# openSX70_LENS_BELLOWS_V5_1-SEEED_2018022.net
KiCad netlist of a schematic drawn in EAGLE
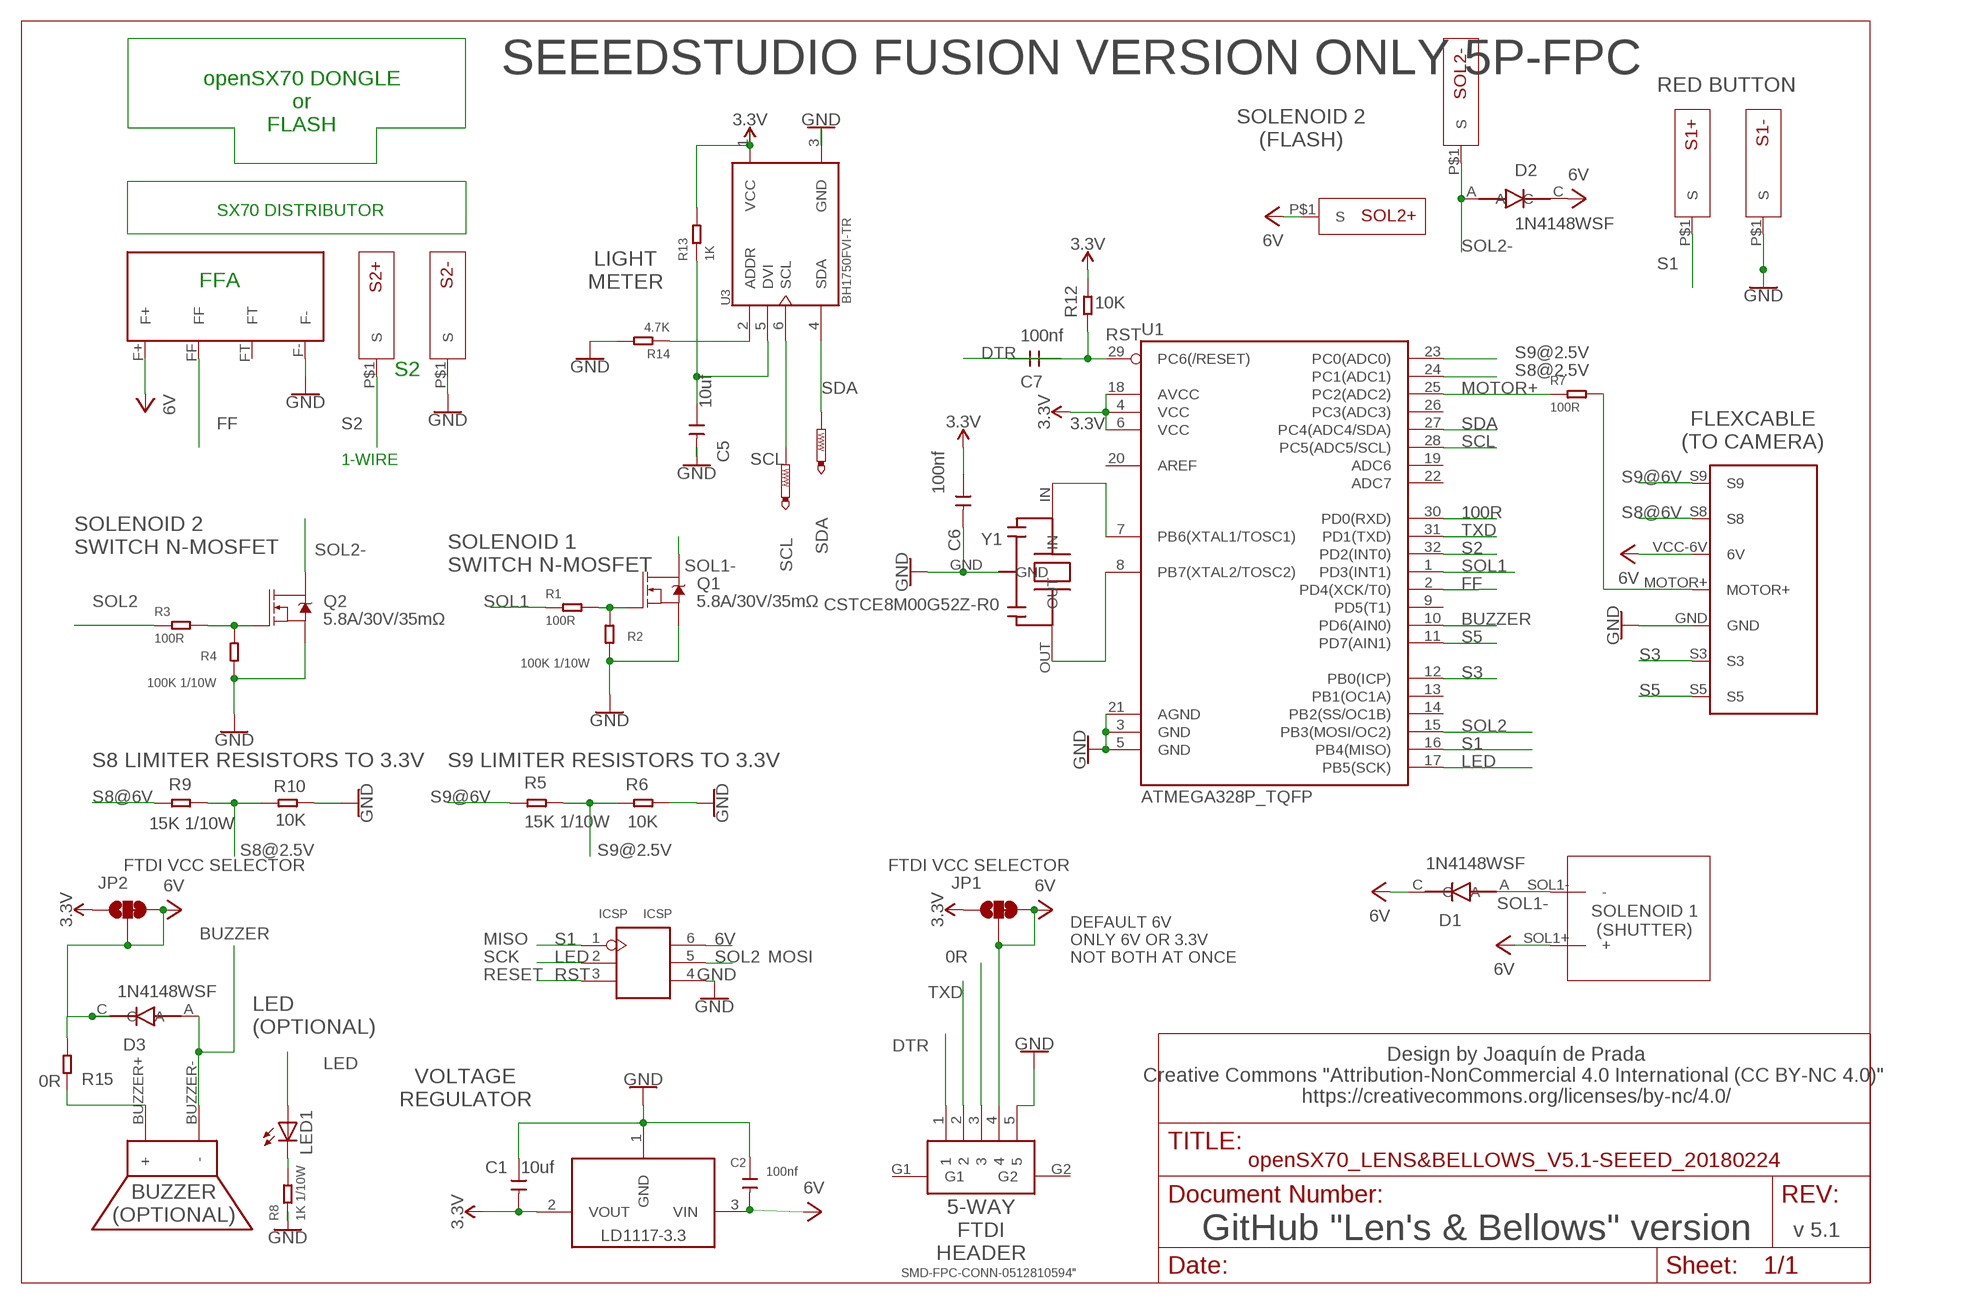
[diagram p0: schematic, sheet 1]

(export (version "E")
  (design (tool "Eeschema 10.0.6"))
  (components
    (comp (ref "C1")
      (value "10uf")
      (footprint "eagle-import:C0603")
      (fields (field (name "MPN") "CC0603KRX5R6BB106"))
      (libsource (lib "eagle-import") (part "CERAMIC-10UF-10V-10%-X5R(0603)"))
    )
    (comp (ref "C2")
      (value "100nf")
      (footprint "eagle-import:C0603")
      (fields (field (name "MPN") "CC0603KRX7R9BB104"))
      (libsource (lib "eagle-import") (part "CERAMIC-100NF-50V-10%-X7R(0603)"))
    )
    (comp (ref "C5")
      (value "10uf")
      (footprint "eagle-import:C0603")
      (fields (field (name "MPN") "CC0603KRX5R6BB106"))
      (libsource (lib "eagle-import") (part "CERAMIC-10UF-10V-10%-X5R(0603)"))
    )
    (comp (ref "C6")
      (value "100nf")
      (footprint "eagle-import:C0603")
      (fields (field (name "MPN") "CC0603KRX7R9BB104"))
      (libsource (lib "eagle-import") (part "CERAMIC-100NF-50V-10%-X7R(0603)"))
    )
    (comp (ref "C7")
      (value "100nf")
      (footprint "eagle-import:C0603")
      (fields (field (name "MPN") "CC0603KRX7R9BB104"))
      (libsource (lib "eagle-import") (part "CERAMIC-100NF-50V-10%-X7R(0603)"))
    )
    (comp (ref "D1")
      (value "1N4148WSF")
      (footprint "eagle-import:SODFL2512X100N")
      (fields (field (name "MANUFACTURER") "Fairchild Semiconductor"))
      (libsource (lib "eagle-import") (part "1N4148WS"))
    )
    (comp (ref "D2")
      (value "1N4148WSF")
      (footprint "eagle-import:SODFL2512X100N")
      (fields (field (name "MANUFACTURER") "Fairchild Semiconductor"))
      (libsource (lib "eagle-import") (part "1N4148WS"))
    )
    (comp (ref "D3")
      (value "1N4148WSF")
      (footprint "eagle-import:SODFL2512X100N")
      (fields (field (name "MANUFACTURER") "Fairchild Semiconductor"))
      (libsource (lib "eagle-import") (part "1N4148WS"))
    )
    (comp (ref "ICSP")
      (value "ICSP")
      (footprint "eagle-import:H2X3-2.54")
      (libsource (lib "eagle-import") (part "ICSP"))
    )
    (comp (ref "JP1")
      (value "FTDI VCC SELECTOR")
      (footprint "eagle-import:SMT-JUMPER_3_1-NC_TRACE_SILK")
      (libsource (lib "eagle-import") (part "JUMPER-SMT_3_1-NC_TRACE_SILK"))
    )
    (comp (ref "JP2")
      (value "FTDI VCC SELECTOR")
      (footprint "eagle-import:SMT-JUMPER_3_1-NC_TRACE_SILK")
      (libsource (lib "eagle-import") (part "JUMPER-SMT_3_1-NC_TRACE_SILK"))
    )
    (comp (ref "LD11172.5V")
      (value "LD1117 2.5V")
      (footprint "eagle-import:SOT223")
      (fields (field (name "MF") "Advanced Monolithic Systems") (field (name "MP") "AMS1117-5.0"))
      (libsource (lib "eagle-import") (part "LD1117-3.3"))
    )
    (comp (ref "LED1")
      (value "LEDCHIPLED_0805")
      (footprint "eagle-import:CHIPLED_0805")
      (libsource (lib "eagle-import") (part "LEDCHIPLED_0805"))
    )
    (comp (ref "Q1")
      (value "5.8A/30V/35mΩ")
      (footprint "eagle-import:SOT23-3")
      (libsource (lib "eagle-import") (part "MOSFET-NCH-AO3404A"))
    )
    (comp (ref "Q2")
      (value "5.8A/30V/35mΩ")
      (footprint "eagle-import:SOT23-3")
      (libsource (lib "eagle-import") (part "MOSFET-NCH-AO3404A"))
    )
    (comp (ref "R1")
      (value "100R")
      (footprint "eagle-import:R0603")
      (fields (field (name "MPN") "RC0603JR-07100RL"))
      (libsource (lib "eagle-import") (part "SMD-RES-100R-5%-1/10W(0603)"))
    )
    (comp (ref "R2")
      (value "100K 1/10W")
      (footprint "eagle-import:R0603")
      (fields (field (name "MPN") "RC0603JR-07100KL"))
      (libsource (lib "eagle-import") (part "SMD-RES-100K-5%-1/10W(0603)"))
    )
    (comp (ref "R3")
      (value "100R")
      (footprint "eagle-import:R0603")
      (fields (field (name "MPN") "RC0603JR-07100RL"))
      (libsource (lib "eagle-import") (part "SMD-RES-100R-5%-1/10W(0603)"))
    )
    (comp (ref "R4")
      (value "100K 1/10W")
      (footprint "eagle-import:R0603")
      (fields (field (name "MPN") "RC0603JR-07100KL"))
      (libsource (lib "eagle-import") (part "SMD-RES-100K-5%-1/10W(0603)"))
    )
    (comp (ref "R5")
      (value "15K 1/10W")
      (footprint "eagle-import:R0603")
      (fields (field (name "MPN") "RC0603FR-0715KL"))
      (libsource (lib "eagle-import") (part "SMD-RES-15K-1%-1/10W(0603)"))
    )
    (comp (ref "R6")
      (value "10K")
      (footprint "eagle-import:R0603")
      (fields (field (name "MPN") "RC0603FR-0710KL"))
      (libsource (lib "eagle-import") (part "SMD-RES-10K-1%-1/10W(0603)"))
    )
    (comp (ref "R7")
      (value "100R")
      (footprint "eagle-import:R0603")
      (fields (field (name "MPN") "RC0603JR-07100RL"))
      (libsource (lib "eagle-import") (part "SMD-RES-100R-5%-1/10W(0603)"))
    )
    (comp (ref "R8")
      (value "1K 1/10W")
      (footprint "eagle-import:R0603")
      (fields (field (name "MPN") "RC0603JR-071KL"))
      (libsource (lib "eagle-import") (part "SMD-RES-1K-5%-1/10W(0603)"))
    )
    (comp (ref "R9")
      (value "15K 1/10W")
      (footprint "eagle-import:R0603")
      (fields (field (name "MPN") "RC0603FR-0715KL"))
      (libsource (lib "eagle-import") (part "SMD-RES-15K-1%-1/10W(0603)"))
    )
    (comp (ref "R10")
      (value "10K")
      (footprint "eagle-import:R0603")
      (fields (field (name "MPN") "RC0603FR-0710KL"))
      (libsource (lib "eagle-import") (part "SMD-RES-10K-1%-1/10W(0603)"))
    )
    (comp (ref "R12")
      (value "10K")
      (footprint "eagle-import:R0603")
      (fields (field (name "MPN") "RC0603FR-0710KL"))
      (libsource (lib "eagle-import") (part "SMD-RES-10K-1%-1/10W(0603)"))
    )
    (comp (ref "R13")
      (value "1K")
      (footprint "eagle-import:R0603")
      (fields (field (name "MPN") "RC0603FR-071KL"))
      (libsource (lib "eagle-import") (part "SMD-RES-1K-1%-1/10W(0603)"))
    )
    (comp (ref "R14")
      (value "4.7K")
      (footprint "eagle-import:R0603")
      (fields (field (name "MPN") "RC0603JR-074K7L"))
      (libsource (lib "eagle-import") (part "SMD-RES-4.7K-5%-1/10W(0603)"))
    )
    (comp (ref "R15")
      (value "0R")
      (footprint "eagle-import:R0603")
      (fields (field (name "MPN") "RC0603JR-07100RL"))
      (libsource (lib "eagle-import") (part "SMD-RES-100R-5%-1/10W(0603)"))
    )
    (comp (ref "S1+")
      (value "SX70-S-PAD-NEW")
      (footprint "eagle-import:SX70-S-PAD2")
      (libsource (lib "eagle-import") (part "SX70-S-PAD-NEW"))
    )
    (comp (ref "S1-")
      (value "SX70-S-PAD-NEW")
      (footprint "eagle-import:SX70-S-PAD2")
      (libsource (lib "eagle-import") (part "SX70-S-PAD-NEW"))
    )
    (comp (ref "S2+")
      (value "SX70-S-PAD-NEW")
      (footprint "eagle-import:SX70-S-PAD2")
      (libsource (lib "eagle-import") (part "SX70-S-PAD-NEW"))
    )
    (comp (ref "S2-")
      (value "SX70-S-PAD-NEW")
      (footprint "eagle-import:SX70-S-PAD2")
      (libsource (lib "eagle-import") (part "SX70-S-PAD-NEW"))
    )
    (comp (ref "SCL")
      (value "PTR1TP08R")
      (footprint "eagle-import:TP08R")
      (libsource (lib "eagle-import") (part "PTR1TP08R"))
    )
    (comp (ref "SDA")
      (value "PTR1TP08R")
      (footprint "eagle-import:TP08R")
      (libsource (lib "eagle-import") (part "PTR1TP08R"))
    )
    (comp (ref "SOL1")
      (value "SX70-SOLENOID1-2PADS")
      (footprint "eagle-import:SX70-SOLENOID1-2")
      (libsource (lib "eagle-import") (part "SX70-SOLENOID1-2PADS"))
    )
    (comp (ref "SOL2+")
      (value "SX70-S-PAD-NEW")
      (footprint "eagle-import:SX70-S-PAD2")
      (libsource (lib "eagle-import") (part "SX70-S-PAD-NEW"))
    )
    (comp (ref "SOL2-")
      (value "SX70-S-PAD-NEW")
      (footprint "eagle-import:SX70-S-PAD2")
      (libsource (lib "eagle-import") (part "SX70-S-PAD-NEW"))
    )
    (comp (ref "U$1")
      (value "SX70-7-PAD")
      (footprint "eagle-import:SX70-7-PAD")
      (libsource (lib "eagle-import") (part "SX70-7-PAD"))
    )
    (comp (ref "U$2")
      (value "FFA")
      (footprint "eagle-import:FFA-PAD-PACKAGE")
      (libsource (lib "eagle-import") (part "SX70-FFA-PAD"))
    )
    (comp (ref "U$3")
      (value "CSET8-5G_V2")
      (footprint "eagle-import:CSET8-5G_PACKAGE")
      (libsource (lib "eagle-import") (part "CSET8-5G_V2"))
    )
    (comp (ref "U$4")
      (value "SMD-FPC-CONN-0512810594\"")
      (footprint "eagle-import:51281-0594")
      (libsource (lib "eagle-import") (part "SMD-FPC-CONN-0512810594{dblquote}"))
    )
    (comp (ref "U1")
      (value "ATMEGA328P_TQFP")
      (footprint "eagle-import:TQFP32-08")
      (libsource (lib "eagle-import") (part "ATMEGA328P_TQFP"))
    )
    (comp (ref "U3")
      (value "BH1750FVI-TR")
      (footprint "eagle-import:SOTFL50P300X75-6N")
      (fields (field (name "MF") "Rohm"))
      (libsource (lib "eagle-import") (part "BH1750FVI-TR"))
    )
    (comp (ref "Y1")
      (value "CSTCE8M00G52Z-R0")
      (footprint "eagle-import:CFP95P160X100-3N")
      (fields (field (name "MF") "Murata") (field (name "MP") "CSTCE16M0V53-R0"))
      (libsource (lib "eagle-import") (part "CSTCE16M0V53-R0"))
    )
  )
  (nets
    (net (code "1") (name "/0R") (class "Default")
      (node (ref "U$4") (pin "3") (pinfunction "3_3") (pintype "bidirectional"))
    )
    (net (code "2") (name "/100R") (class "Default")
      (node (ref "U1") (pin "30") (pinfunction "PD0(RXD)_30") (pintype "bidirectional"))
    )
    (net (code "3") (name "/BUZZER") (class "Default")
      (node (ref "D3") (pin "A") (pinfunction "A_A") (pintype "passive"))
      (node (ref "U$3") (pin "BUZZER-") (pinfunction "-_BUZZER-") (pintype "bidirectional"))
      (node (ref "U1") (pin "10") (pinfunction "PD6(AIN0)_10") (pintype "bidirectional"))
    )
    (net (code "4") (name "/DTR") (class "Default")
      (node (ref "C7") (pin "1") (pinfunction "1_1") (pintype "passive"))
      (node (ref "U$4") (pin "1") (pinfunction "1_1") (pintype "bidirectional"))
    )
    (net (code "5") (name "/FF") (class "Default")
      (node (ref "U$2") (pin "FF") (pinfunction "FF_FF") (pintype "bidirectional"))
      (node (ref "U1") (pin "2") (pinfunction "PD4(XCK/T0)_2") (pintype "bidirectional"))
    )
    (net (code "6") (name "/LED") (class "Default")
      (node (ref "ICSP") (pin "2") (pinfunction "SCK_2") (pintype "bidirectional"))
      (node (ref "LED1") (pin "A") (pinfunction "A_A") (pintype "passive"))
      (node (ref "U1") (pin "17") (pinfunction "PB5(SCK)_17") (pintype "bidirectional"))
    )
    (net (code "7") (name "/MOTOR+") (class "Default")
      (node (ref "R7") (pin "1") (pinfunction "1_1") (pintype "passive"))
      (node (ref "U1") (pin "25") (pinfunction "PC2(ADC2)_25") (pintype "bidirectional"))
    )
    (net (code "8") (name "/RST") (class "Default")
      (node (ref "C7") (pin "2") (pinfunction "2_2") (pintype "passive"))
      (node (ref "ICSP") (pin "3") (pinfunction "RST_3") (pintype "bidirectional"))
      (node (ref "R12") (pin "1") (pinfunction "1_1") (pintype "passive"))
      (node (ref "U1") (pin "29") (pinfunction "PC6(/RESET)_29") (pintype "bidirectional"))
    )
    (net (code "9") (name "/S1") (class "Default")
      (node (ref "ICSP") (pin "1") (pinfunction "MISO_1") (pintype "bidirectional"))
      (node (ref "S1+") (pin "P$1") (pinfunction "S_P$1") (pintype "bidirectional"))
      (node (ref "U1") (pin "16") (pinfunction "PB4(MISO)_16") (pintype "bidirectional"))
    )
    (net (code "10") (name "/S2") (class "Default")
      (node (ref "S2+") (pin "P$1") (pinfunction "S_P$1") (pintype "bidirectional"))
      (node (ref "U1") (pin "32") (pinfunction "PD2(INT0)_32") (pintype "bidirectional"))
    )
    (net (code "11") (name "/S3") (class "Default")
      (node (ref "U$1") (pin "S3") (pinfunction "S3_S3") (pintype "bidirectional"))
      (node (ref "U1") (pin "12") (pinfunction "PB0(ICP)_12") (pintype "bidirectional"))
    )
    (net (code "12") (name "/S5") (class "Default")
      (node (ref "U$1") (pin "S5") (pinfunction "S5_S5") (pintype "bidirectional"))
      (node (ref "U1") (pin "11") (pinfunction "PD7(AIN1)_11") (pintype "bidirectional"))
    )
    (net (code "13") (name "/S8@2.5V") (class "Default")
      (node (ref "R10") (pin "1") (pinfunction "1_1") (pintype "passive"))
      (node (ref "R9") (pin "2") (pinfunction "2_2") (pintype "passive"))
      (node (ref "U1") (pin "24") (pinfunction "PC1(ADC1)_24") (pintype "bidirectional"))
    )
    (net (code "14") (name "/S8@6V") (class "Default")
      (node (ref "R9") (pin "1") (pinfunction "1_1") (pintype "passive"))
      (node (ref "U$1") (pin "S8") (pinfunction "S8_S8") (pintype "bidirectional"))
    )
    (net (code "15") (name "/S9@2.5V") (class "Default")
      (node (ref "R5") (pin "2") (pinfunction "2_2") (pintype "passive"))
      (node (ref "R6") (pin "1") (pinfunction "1_1") (pintype "passive"))
      (node (ref "U1") (pin "23") (pinfunction "PC0(ADC0)_23") (pintype "bidirectional"))
    )
    (net (code "16") (name "/S9@6V") (class "Default")
      (node (ref "R5") (pin "1") (pinfunction "1_1") (pintype "passive"))
      (node (ref "U$1") (pin "S9") (pinfunction "S9_S9") (pintype "bidirectional"))
    )
    (net (code "17") (name "/SCL") (class "Default")
      (node (ref "SCL") (pin "TP") (pinfunction "TP_TP") (pintype "input"))
      (node (ref "U1") (pin "28") (pinfunction "PC5(ADC5/SCL)_28") (pintype "bidirectional"))
      (node (ref "U3") (pin "6") (pinfunction "SCL_6") (pintype "input"))
    )
    (net (code "18") (name "/SDA") (class "Default")
      (node (ref "SDA") (pin "TP") (pinfunction "TP_TP") (pintype "input"))
      (node (ref "U1") (pin "27") (pinfunction "PC4(ADC4/SDA)_27") (pintype "bidirectional"))
      (node (ref "U3") (pin "4") (pinfunction "SDA_4") (pintype "bidirectional"))
    )
    (net (code "19") (name "/SOL1") (class "Default")
      (node (ref "R1") (pin "1") (pinfunction "1_1") (pintype "passive"))
      (node (ref "U1") (pin "1") (pinfunction "PD3(INT1)_1") (pintype "bidirectional"))
    )
    (net (code "20") (name "/SOL1-") (class "Default")
      (node (ref "D1") (pin "A") (pinfunction "A_A") (pintype "passive"))
      (node (ref "Q1") (pin "3") (pinfunction "D_3") (pintype "bidirectional"))
      (node (ref "SOL1") (pin "SOL1-") (pinfunction "-_SOL1-") (pintype "bidirectional"))
    )
    (net (code "21") (name "/SOL2") (class "Default")
      (node (ref "ICSP") (pin "5") (pinfunction "MOSI_5") (pintype "bidirectional"))
      (node (ref "R3") (pin "1") (pinfunction "1_1") (pintype "passive"))
      (node (ref "U1") (pin "15") (pinfunction "PB3(MOSI/OC2)_15") (pintype "bidirectional"))
    )
    (net (code "22") (name "/SOL2-") (class "Default")
      (node (ref "D2") (pin "A") (pinfunction "A_A") (pintype "passive"))
      (node (ref "Q2") (pin "3") (pinfunction "D_3") (pintype "bidirectional"))
      (node (ref "SOL2-") (pin "P$1") (pinfunction "S_P$1") (pintype "bidirectional"))
    )
    (net (code "23") (name "/TXD") (class "Default")
      (node (ref "U$4") (pin "2") (pinfunction "2_2") (pintype "bidirectional"))
      (node (ref "U1") (pin "31") (pinfunction "PD1(TXD)_31") (pintype "bidirectional"))
    )
    (net (code "24") (name "3.3V") (class "Default")
      (node (ref "C1") (pin "2") (pinfunction "2_2") (pintype "passive"))
      (node (ref "C6") (pin "1") (pinfunction "1_1") (pintype "passive"))
      (node (ref "JP1") (pin "1") (pinfunction "1_1") (pintype "passive"))
      (node (ref "JP2") (pin "1") (pinfunction "1_1") (pintype "passive"))
      (node (ref "LD11172.5V") (pin "2") (pinfunction "VOUT_2") (pintype "bidirectional"))
      (node (ref "R12") (pin "2") (pinfunction "2_2") (pintype "passive"))
      (node (ref "R13") (pin "2") (pinfunction "2_2") (pintype "passive"))
      (node (ref "U1") (pin "18") (pinfunction "AVCC_18") (pintype "bidirectional"))
      (node (ref "U1") (pin "4") (pinfunction "VCC_4") (pintype "bidirectional"))
      (node (ref "U1") (pin "6") (pinfunction "VCC_6") (pintype "bidirectional"))
      (node (ref "U3") (pin "1") (pinfunction "VCC_1") (pintype "power_in"))
    )
    (net (code "25") (name "6V") (class "Default")
      (node (ref "C2") (pin "2") (pinfunction "2_2") (pintype "passive"))
      (node (ref "D1") (pin "C") (pinfunction "C_C") (pintype "passive"))
      (node (ref "D2") (pin "C") (pinfunction "C_C") (pintype "passive"))
      (node (ref "D3") (pin "C") (pinfunction "C_C") (pintype "passive"))
      (node (ref "ICSP") (pin "6") (pinfunction "VCC_6") (pintype "bidirectional"))
      (node (ref "JP1") (pin "2") (pinfunction "2_2") (pintype "passive"))
      (node (ref "JP1") (pin "3") (pinfunction "3_3") (pintype "passive"))
      (node (ref "JP2") (pin "2") (pinfunction "2_2") (pintype "passive"))
      (node (ref "JP2") (pin "3") (pinfunction "3_3") (pintype "passive"))
      (node (ref "LD11172.5V") (pin "3") (pinfunction "VIN_3") (pintype "bidirectional"))
      (node (ref "R15") (pin "2") (pinfunction "2_2") (pintype "passive"))
      (node (ref "SOL1") (pin "SOL1+") (pinfunction "+_SOL1+") (pintype "bidirectional"))
      (node (ref "SOL2+") (pin "P$1") (pinfunction "S_P$1") (pintype "bidirectional"))
      (node (ref "U$1") (pin "VCC-6V") (pinfunction "6V_VCC-6V") (pintype "bidirectional"))
      (node (ref "U$2") (pin "F+") (pinfunction "F+_F+") (pintype "bidirectional"))
      (node (ref "U$4") (pin "4") (pinfunction "4_4") (pintype "bidirectional"))
    )
    (net (code "26") (name "GND") (class "Default")
      (node (ref "C1") (pin "1") (pinfunction "1_1") (pintype "passive"))
      (node (ref "C2") (pin "1") (pinfunction "1_1") (pintype "passive"))
      (node (ref "C5") (pin "2") (pinfunction "2_2") (pintype "passive"))
      (node (ref "C6") (pin "2") (pinfunction "2_2") (pintype "passive"))
      (node (ref "ICSP") (pin "4") (pinfunction "GND_4") (pintype "bidirectional"))
      (node (ref "LD11172.5V") (pin "1") (pinfunction "GND_1") (pintype "bidirectional"))
      (node (ref "Q1") (pin "2") (pinfunction "S_2") (pintype "bidirectional"))
      (node (ref "Q2") (pin "2") (pinfunction "S_2") (pintype "bidirectional"))
      (node (ref "R10") (pin "2") (pinfunction "2_2") (pintype "passive"))
      (node (ref "R14") (pin "2") (pinfunction "2_2") (pintype "passive"))
      (node (ref "R2") (pin "1") (pinfunction "1_1") (pintype "passive"))
      (node (ref "R4") (pin "1") (pinfunction "1_1") (pintype "passive"))
      (node (ref "R6") (pin "2") (pinfunction "2_2") (pintype "passive"))
      (node (ref "R8") (pin "1") (pinfunction "1_1") (pintype "passive"))
      (node (ref "S1-") (pin "P$1") (pinfunction "S_P$1") (pintype "bidirectional"))
      (node (ref "S2-") (pin "P$1") (pinfunction "S_P$1") (pintype "bidirectional"))
      (node (ref "U$1") (pin "GND") (pinfunction "GND_GND") (pintype "bidirectional"))
      (node (ref "U$2") (pin "F-") (pinfunction "F-_F-") (pintype "bidirectional"))
      (node (ref "U$4") (pin "5") (pinfunction "5_5") (pintype "bidirectional"))
      (node (ref "U1") (pin "21") (pinfunction "AGND_21") (pintype "bidirectional"))
      (node (ref "U1") (pin "3") (pinfunction "GND_3") (pintype "bidirectional"))
      (node (ref "U1") (pin "5") (pinfunction "GND_5") (pintype "bidirectional"))
      (node (ref "U3") (pin "3") (pinfunction "GND_3") (pintype "power_in"))
      (node (ref "Y1") (pin "GND") (pinfunction "GND_GND") (pintype "passive"))
    )
    (net (code "27") (name "Net-(LED1-PadC)") (class "Default")
      (node (ref "LED1") (pin "C") (pinfunction "C_C") (pintype "passive"))
      (node (ref "R8") (pin "2") (pinfunction "2_2") (pintype "passive"))
    )
    (net (code "28") (name "Net-(Q1-G)") (class "Default")
      (node (ref "Q1") (pin "1") (pinfunction "G_1") (pintype "bidirectional"))
      (node (ref "R1") (pin "2") (pinfunction "2_2") (pintype "passive"))
      (node (ref "R2") (pin "2") (pinfunction "2_2") (pintype "passive"))
    )
    (net (code "29") (name "Net-(Q2-G)") (class "Default")
      (node (ref "Q2") (pin "1") (pinfunction "G_1") (pintype "bidirectional"))
      (node (ref "R3") (pin "2") (pinfunction "2_2") (pintype "passive"))
      (node (ref "R4") (pin "2") (pinfunction "2_2") (pintype "passive"))
    )
    (net (code "30") (name "Net-(R7-Pad2)") (class "Default")
      (node (ref "R7") (pin "2") (pinfunction "2_2") (pintype "passive"))
      (node (ref "U$1") (pin "MOTOR+") (pinfunction "MOTOR+_MOTOR+") (pintype "bidirectional"))
    )
    (net (code "31") (name "Net-(U$3-+)") (class "Default")
      (node (ref "R15") (pin "1") (pinfunction "1_1") (pintype "passive"))
      (node (ref "U$3") (pin "BUZZER+") (pinfunction "+_BUZZER+") (pintype "bidirectional"))
    )
    (net (code "32") (name "Net-(U1-PB6(XTAL1{slash}TOSC1))") (class "Default")
      (node (ref "U1") (pin "7") (pinfunction "PB6(XTAL1/TOSC1)_7") (pintype "bidirectional"))
      (node (ref "Y1") (pin "IN") (pinfunction "IN_IN") (pintype "input"))
    )
    (net (code "33") (name "Net-(U1-PB7(XTAL2{slash}TOSC2))") (class "Default")
      (node (ref "U1") (pin "8") (pinfunction "PB7(XTAL2/TOSC2)_8") (pintype "bidirectional"))
      (node (ref "Y1") (pin "OUT") (pinfunction "OUT_OUT") (pintype "output"))
    )
    (net (code "34") (name "Net-(U3-ADDR)") (class "Default")
      (node (ref "R14") (pin "1") (pinfunction "1_1") (pintype "passive"))
      (node (ref "U3") (pin "2") (pinfunction "ADDR_2") (pintype "input"))
    )
    (net (code "35") (name "Net-(U3-DVI)") (class "Default")
      (node (ref "C5") (pin "1") (pinfunction "1_1") (pintype "passive"))
      (node (ref "R13") (pin "1") (pinfunction "1_1") (pintype "passive"))
      (node (ref "U3") (pin "5") (pinfunction "DVI_5") (pintype "input"))
    )
    (net (code "36") (name "unconnected-(U$2-PadFT)") (class "Default")
      (node (ref "U$2") (pin "FT") (pinfunction "FT_FT") (pintype "bidirectional"))
    )
    (net (code "37") (name "unconnected-(U$4-PadG1)") (class "Default")
      (node (ref "U$4") (pin "G1") (pinfunction "G1_G1") (pintype "bidirectional"))
    )
    (net (code "38") (name "unconnected-(U$4-PadG2)") (class "Default")
      (node (ref "U$4") (pin "G2") (pinfunction "G2_G2") (pintype "bidirectional"))
    )
    (net (code "39") (name "unconnected-(U1-ADC6-Pad19)") (class "Default")
      (node (ref "U1") (pin "19") (pinfunction "ADC6_19") (pintype "bidirectional"))
    )
    (net (code "40") (name "unconnected-(U1-ADC7-Pad22)") (class "Default")
      (node (ref "U1") (pin "22") (pinfunction "ADC7_22") (pintype "bidirectional"))
    )
    (net (code "41") (name "unconnected-(U1-AREF-Pad20)") (class "Default")
      (node (ref "U1") (pin "20") (pinfunction "AREF_20") (pintype "bidirectional"))
    )
    (net (code "42") (name "unconnected-(U1-PB1(OC1A)-Pad13)") (class "Default")
      (node (ref "U1") (pin "13") (pinfunction "PB1(OC1A)_13") (pintype "bidirectional"))
    )
    (net (code "43") (name "unconnected-(U1-PB2(SS{slash}OC1B)-Pad14)") (class "Default")
      (node (ref "U1") (pin "14") (pinfunction "PB2(SS/OC1B)_14") (pintype "bidirectional"))
    )
    (net (code "44") (name "unconnected-(U1-PC3(ADC3)-Pad26)") (class "Default")
      (node (ref "U1") (pin "26") (pinfunction "PC3(ADC3)_26") (pintype "bidirectional"))
    )
    (net (code "45") (name "unconnected-(U1-PD5(T1)-Pad9)") (class "Default")
      (node (ref "U1") (pin "9") (pinfunction "PD5(T1)_9") (pintype "bidirectional"))
    )
  )
)
